# PEC11D_dual_rotary_enc_test.net
KiCad netlist of a schematic drawn in EAGLE
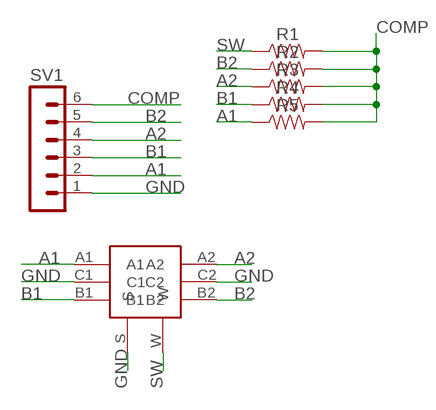
[diagram p0: schematic, sheet 1]

(export (version "E")
  (design (tool "Eeschema 10.0.6"))
  (components
    (comp (ref "R1")
      (value "RESISTOR21206")
      (footprint "eagle-import:1206")
      (libsource (lib "eagle-import") (part "RESISTOR21206"))
    )
    (comp (ref "R2")
      (value "RESISTOR21206")
      (footprint "eagle-import:1206")
      (libsource (lib "eagle-import") (part "RESISTOR21206"))
    )
    (comp (ref "R3")
      (value "RESISTOR21206")
      (footprint "eagle-import:1206")
      (libsource (lib "eagle-import") (part "RESISTOR21206"))
    )
    (comp (ref "R4")
      (value "RESISTOR21206")
      (footprint "eagle-import:1206")
      (libsource (lib "eagle-import") (part "RESISTOR21206"))
    )
    (comp (ref "R5")
      (value "RESISTOR21206")
      (footprint "eagle-import:1206")
      (libsource (lib "eagle-import") (part "RESISTOR21206"))
    )
    (comp (ref "SV1")
      (value "MA06-1")
      (footprint "eagle-import:MA06-1")
      (libsource (lib "eagle-import") (part "MA06-1"))
    )
    (comp (ref "U$1")
      (value "PEC11DPEC11D")
      (footprint "eagle-import:PEC11D_TH")
      (libsource (lib "eagle-import") (part "PEC11DPEC11D"))
    )
  )
  (nets
    (net (code "1") (name "/A1") (class "Default")
      (node (ref "R5") (pin "1") (pinfunction "1_1") (pintype "passive"))
      (node (ref "SV1") (pin "2") (pinfunction "2_2") (pintype "passive"))
      (node (ref "U$1") (pin "A1") (pinfunction "A1_A1") (pintype "bidirectional"))
    )
    (net (code "2") (name "/A2") (class "Default")
      (node (ref "R3") (pin "1") (pinfunction "1_1") (pintype "passive"))
      (node (ref "SV1") (pin "4") (pinfunction "4_4") (pintype "passive"))
      (node (ref "U$1") (pin "A2") (pinfunction "A2_A2") (pintype "bidirectional"))
    )
    (net (code "3") (name "/B1") (class "Default")
      (node (ref "R4") (pin "1") (pinfunction "1_1") (pintype "passive"))
      (node (ref "SV1") (pin "3") (pinfunction "3_3") (pintype "passive"))
      (node (ref "U$1") (pin "B1") (pinfunction "B1_B1") (pintype "bidirectional"))
    )
    (net (code "4") (name "/B2") (class "Default")
      (node (ref "R2") (pin "1") (pinfunction "1_1") (pintype "passive"))
      (node (ref "SV1") (pin "5") (pinfunction "5_5") (pintype "passive"))
      (node (ref "U$1") (pin "B2") (pinfunction "B2_B2") (pintype "bidirectional"))
    )
    (net (code "5") (name "/COMP") (class "Default")
      (node (ref "R1") (pin "2") (pinfunction "2_2") (pintype "passive"))
      (node (ref "R2") (pin "2") (pinfunction "2_2") (pintype "passive"))
      (node (ref "R3") (pin "2") (pinfunction "2_2") (pintype "passive"))
      (node (ref "R4") (pin "2") (pinfunction "2_2") (pintype "passive"))
      (node (ref "R5") (pin "2") (pinfunction "2_2") (pintype "passive"))
      (node (ref "SV1") (pin "6") (pinfunction "6_6") (pintype "passive"))
    )
    (net (code "6") (name "/GND") (class "Default")
      (node (ref "SV1") (pin "1") (pinfunction "1_1") (pintype "passive"))
      (node (ref "U$1") (pin "C1") (pinfunction "C1_C1") (pintype "bidirectional"))
      (node (ref "U$1") (pin "C2") (pinfunction "C2_C2") (pintype "bidirectional"))
      (node (ref "U$1") (pin "S") (pinfunction "S_S") (pintype "bidirectional"))
    )
    (net (code "7") (name "/SW") (class "Default")
      (node (ref "R1") (pin "1") (pinfunction "1_1") (pintype "passive"))
      (node (ref "U$1") (pin "W") (pinfunction "W_W") (pintype "bidirectional"))
    )
  )
)
